# rk1robot_v0_5.net
KiCad netlist of a schematic drawn in EAGLE
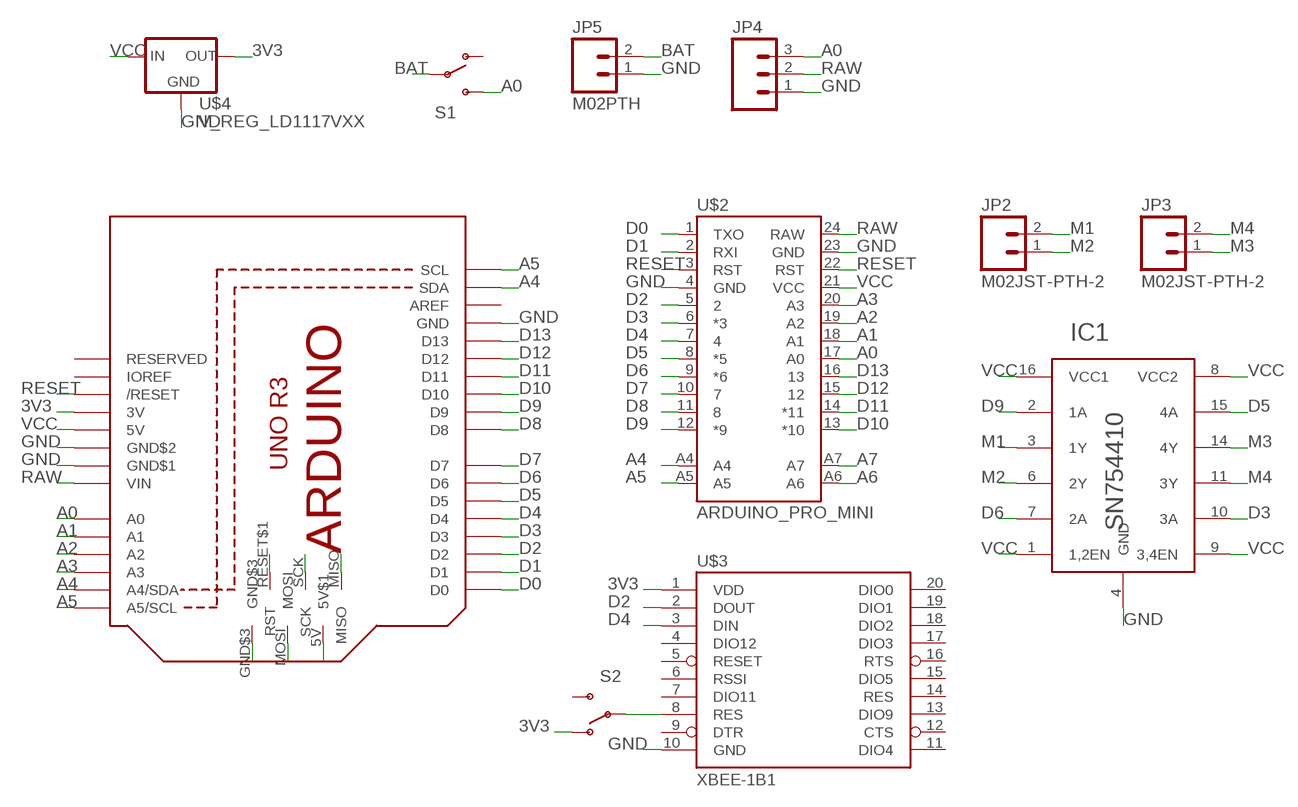
[diagram p0: schematic, sheet 1]

(export (version "E")
  (design (tool "Eeschema 10.0.6"))
  (components
    (comp (ref "IC1")
      (value "SN754410")
      (footprint "eagle-import:DIL16")
      (libsource (lib "eagle-import") (part "SN754410"))
    )
    (comp (ref "JP2")
      (value "M02JST-PTH-2")
      (footprint "eagle-import:JST-2-PTH")
      (libsource (lib "eagle-import") (part "M02JST-PTH-2"))
    )
    (comp (ref "JP3")
      (value "M02JST-PTH-2")
      (footprint "eagle-import:JST-2-PTH")
      (libsource (lib "eagle-import") (part "M02JST-PTH-2"))
    )
    (comp (ref "JP4")
      (value "M03PTH")
      (footprint "eagle-import:1X03")
      (libsource (lib "eagle-import") (part "M03PTH"))
    )
    (comp (ref "JP5")
      (value "M02PTH")
      (footprint "eagle-import:1X02")
      (libsource (lib "eagle-import") (part "M02PTH"))
    )
    (comp (ref "S1")
      (value "SWITCH-SPDTPTH")
      (footprint "eagle-import:SWITCH-SPDT")
      (libsource (lib "eagle-import") (part "SWITCH-SPDTPTH"))
    )
    (comp (ref "S2")
      (value "SWITCH-SPDTPTH")
      (footprint "eagle-import:SWITCH-SPDT")
      (libsource (lib "eagle-import") (part "SWITCH-SPDTPTH"))
    )
    (comp (ref "U$1")
      (value "ARDUINO_R3_ICSP")
      (footprint "eagle-import:ARDUINOR3_ICSP")
      (libsource (lib "eagle-import") (part "ARDUINO_R3_ICSP"))
    )
    (comp (ref "U$2")
      (value "ARDUINO_PRO_MINI")
      (footprint "eagle-import:ARDUINO_PRO_MINI")
      (libsource (lib "eagle-import") (part "ARDUINO_PRO_MINI"))
    )
    (comp (ref "U$3")
      (value "XBEE-1B1")
      (footprint "eagle-import:XBEE-1")
      (libsource (lib "eagle-import") (part "XBEE-1B1"))
    )
    (comp (ref "U$4")
      (value "V_REG_LD1117VXX")
      (footprint "eagle-import:78XXL")
      (libsource (lib "eagle-import") (part "V_REG_LD1117VXX"))
    )
  )
  (nets
    (net (code "1") (name "/3V3") (class "Default")
      (node (ref "S2") (pin "1") (pinfunction "O_1") (pintype "passive"))
      (node (ref "U$1") (pin "3V") (pinfunction "3V_3V") (pintype "power_in"))
      (node (ref "U$3") (pin "1") (pinfunction "VDD_1") (pintype "power_in"))
      (node (ref "U$4") (pin "GND") (pinfunction "OUT_GND") (pintype "output"))
    )
    (net (code "2") (name "/A0") (class "Default")
      (node (ref "JP4") (pin "3") (pinfunction "3_3") (pintype "passive"))
      (node (ref "S1") (pin "3") (pinfunction "S_3") (pintype "passive"))
      (node (ref "U$1") (pin "A0") (pinfunction "A0_A0") (pintype "bidirectional"))
      (node (ref "U$2") (pin "17") (pinfunction "A0_17") (pintype "bidirectional"))
    )
    (net (code "3") (name "/A1") (class "Default")
      (node (ref "U$1") (pin "A1") (pinfunction "A1_A1") (pintype "bidirectional"))
      (node (ref "U$2") (pin "18") (pinfunction "A1_18") (pintype "bidirectional"))
    )
    (net (code "4") (name "/A2") (class "Default")
      (node (ref "U$1") (pin "A2") (pinfunction "A2_A2") (pintype "bidirectional"))
      (node (ref "U$2") (pin "19") (pinfunction "A2_19") (pintype "bidirectional"))
    )
    (net (code "5") (name "/A3") (class "Default")
      (node (ref "U$1") (pin "A3") (pinfunction "A3_A3") (pintype "bidirectional"))
      (node (ref "U$2") (pin "20") (pinfunction "A3_20") (pintype "bidirectional"))
    )
    (net (code "6") (name "/A4") (class "Default")
      (node (ref "U$1") (pin "A4") (pinfunction "A4/SDA_A4") (pintype "bidirectional"))
      (node (ref "U$1") (pin "SDA") (pinfunction "SDA_SDA") (pintype "bidirectional"))
      (node (ref "U$2") (pin "A4") (pinfunction "A4_A4") (pintype "bidirectional"))
    )
    (net (code "7") (name "/A5") (class "Default")
      (node (ref "U$1") (pin "A5") (pinfunction "A5/SCL_A5") (pintype "bidirectional"))
      (node (ref "U$1") (pin "SCL") (pinfunction "SCL_SCL") (pintype "bidirectional"))
      (node (ref "U$2") (pin "A5") (pinfunction "A5_A5") (pintype "bidirectional"))
    )
    (net (code "8") (name "/A6") (class "Default")
      (node (ref "U$2") (pin "A6") (pinfunction "A6_A6") (pintype "bidirectional"))
    )
    (net (code "9") (name "/A7") (class "Default")
      (node (ref "U$2") (pin "A7") (pinfunction "A7_A7") (pintype "bidirectional"))
    )
    (net (code "10") (name "/BAT") (class "Default")
      (node (ref "JP5") (pin "2") (pinfunction "2_2") (pintype "passive"))
      (node (ref "S1") (pin "2") (pinfunction "P_2") (pintype "passive"))
    )
    (net (code "11") (name "/D0") (class "Default")
      (node (ref "U$1") (pin "D0") (pinfunction "D0_D0") (pintype "bidirectional"))
      (node (ref "U$2") (pin "1") (pinfunction "TXO_1") (pintype "bidirectional"))
    )
    (net (code "12") (name "/D1") (class "Default")
      (node (ref "U$1") (pin "D1") (pinfunction "D1_D1") (pintype "bidirectional"))
      (node (ref "U$2") (pin "2") (pinfunction "RXI_2") (pintype "bidirectional"))
    )
    (net (code "13") (name "/D2") (class "Default")
      (node (ref "U$1") (pin "D2") (pinfunction "D2_D2") (pintype "bidirectional"))
      (node (ref "U$2") (pin "5") (pinfunction "2_5") (pintype "bidirectional"))
      (node (ref "U$3") (pin "2") (pinfunction "DOUT_2") (pintype "output"))
    )
    (net (code "14") (name "/D3") (class "Default")
      (node (ref "IC1") (pin "10") (pinfunction "3A_10") (pintype "bidirectional"))
      (node (ref "U$1") (pin "D3") (pinfunction "D3_D3") (pintype "bidirectional"))
      (node (ref "U$2") (pin "6") (pinfunction "*3_6") (pintype "bidirectional"))
    )
    (net (code "15") (name "/D4") (class "Default")
      (node (ref "U$1") (pin "D4") (pinfunction "D4_D4") (pintype "bidirectional"))
      (node (ref "U$2") (pin "7") (pinfunction "4_7") (pintype "bidirectional"))
      (node (ref "U$3") (pin "3") (pinfunction "DIN_3") (pintype "input"))
    )
    (net (code "16") (name "/D5") (class "Default")
      (node (ref "IC1") (pin "15") (pinfunction "4A_15") (pintype "bidirectional"))
      (node (ref "U$1") (pin "D5") (pinfunction "D5_D5") (pintype "bidirectional"))
      (node (ref "U$2") (pin "8") (pinfunction "*5_8") (pintype "bidirectional"))
    )
    (net (code "17") (name "/D6") (class "Default")
      (node (ref "IC1") (pin "7") (pinfunction "2A_7") (pintype "bidirectional"))
      (node (ref "U$1") (pin "D6") (pinfunction "D6_D6") (pintype "bidirectional"))
      (node (ref "U$2") (pin "9") (pinfunction "*6_9") (pintype "bidirectional"))
    )
    (net (code "18") (name "/D7") (class "Default")
      (node (ref "U$1") (pin "D7") (pinfunction "D7_D7") (pintype "bidirectional"))
      (node (ref "U$2") (pin "10") (pinfunction "7_10") (pintype "bidirectional"))
    )
    (net (code "19") (name "/D8") (class "Default")
      (node (ref "U$1") (pin "D8") (pinfunction "D8_D8") (pintype "bidirectional"))
      (node (ref "U$2") (pin "11") (pinfunction "8_11") (pintype "bidirectional"))
    )
    (net (code "20") (name "/D9") (class "Default")
      (node (ref "IC1") (pin "2") (pinfunction "1A_2") (pintype "bidirectional"))
      (node (ref "U$1") (pin "D9") (pinfunction "D9_D9") (pintype "bidirectional"))
      (node (ref "U$2") (pin "12") (pinfunction "*9_12") (pintype "bidirectional"))
    )
    (net (code "21") (name "/D10") (class "Default")
      (node (ref "U$1") (pin "D10") (pinfunction "D10_D10") (pintype "bidirectional"))
      (node (ref "U$2") (pin "13") (pinfunction "*10_13") (pintype "bidirectional"))
    )
    (net (code "22") (name "/D11") (class "Default")
      (node (ref "U$1") (pin "D11") (pinfunction "D11_D11") (pintype "bidirectional"))
      (node (ref "U$1") (pin "MOSI") (pinfunction "MOSI_MOSI") (pintype "passive"))
      (node (ref "U$2") (pin "14") (pinfunction "*11_14") (pintype "bidirectional"))
    )
    (net (code "23") (name "/D12") (class "Default")
      (node (ref "U$1") (pin "D12") (pinfunction "D12_D12") (pintype "bidirectional"))
      (node (ref "U$1") (pin "MISO") (pinfunction "MISO_MISO") (pintype "passive"))
      (node (ref "U$2") (pin "15") (pinfunction "12_15") (pintype "bidirectional"))
    )
    (net (code "24") (name "/D13") (class "Default")
      (node (ref "U$1") (pin "D13") (pinfunction "D13_D13") (pintype "bidirectional"))
      (node (ref "U$1") (pin "SCK") (pinfunction "SCK_SCK") (pintype "passive"))
      (node (ref "U$2") (pin "16") (pinfunction "13_16") (pintype "bidirectional"))
    )
    (net (code "25") (name "/GND") (class "Default")
      (node (ref "IC1") (pin "4") (pinfunction "GND_4") (pintype "power_in"))
      (node (ref "JP4") (pin "1") (pinfunction "1_1") (pintype "passive"))
      (node (ref "JP5") (pin "1") (pinfunction "1_1") (pintype "passive"))
      (node (ref "U$1") (pin "GND") (pinfunction "GND_GND") (pintype "power_in"))
      (node (ref "U$1") (pin "GND$1") (pinfunction "GND$1_GND$1") (pintype "power_in"))
      (node (ref "U$1") (pin "GND$2") (pinfunction "GND$2_GND$2") (pintype "power_in"))
      (node (ref "U$1") (pin "GND$3") (pinfunction "GND$3_GND$3") (pintype "passive"))
      (node (ref "U$2") (pin "23") (pinfunction "GND_23") (pintype "bidirectional"))
      (node (ref "U$2") (pin "4") (pinfunction "GND_4") (pintype "bidirectional"))
      (node (ref "U$3") (pin "10") (pinfunction "GND_10") (pintype "power_in"))
      (node (ref "U$4") (pin "IN") (pinfunction "GND_IN") (pintype "input"))
    )
    (net (code "26") (name "/M1") (class "Default")
      (node (ref "IC1") (pin "3") (pinfunction "1Y_3") (pintype "bidirectional"))
      (node (ref "JP2") (pin "2") (pinfunction "2_2") (pintype "passive"))
    )
    (net (code "27") (name "/M2") (class "Default")
      (node (ref "IC1") (pin "6") (pinfunction "2Y_6") (pintype "bidirectional"))
      (node (ref "JP2") (pin "1") (pinfunction "1_1") (pintype "passive"))
    )
    (net (code "28") (name "/M3") (class "Default")
      (node (ref "IC1") (pin "14") (pinfunction "4Y_14") (pintype "bidirectional"))
      (node (ref "JP3") (pin "1") (pinfunction "1_1") (pintype "passive"))
    )
    (net (code "29") (name "/M4") (class "Default")
      (node (ref "IC1") (pin "11") (pinfunction "3Y_11") (pintype "bidirectional"))
      (node (ref "JP3") (pin "2") (pinfunction "2_2") (pintype "passive"))
    )
    (net (code "30") (name "/RAW") (class "Default")
      (node (ref "JP4") (pin "2") (pinfunction "2_2") (pintype "passive"))
      (node (ref "U$1") (pin "VIN") (pinfunction "VIN_VIN") (pintype "power_in"))
      (node (ref "U$2") (pin "24") (pinfunction "RAW_24") (pintype "bidirectional"))
    )
    (net (code "31") (name "/RESET") (class "Default")
      (node (ref "U$1") (pin "RESET") (pinfunction "/RESET_RESET") (pintype "bidirectional"))
      (node (ref "U$1") (pin "RESET$1") (pinfunction "RST_RESET$1") (pintype "passive"))
      (node (ref "U$2") (pin "22") (pinfunction "RST_22") (pintype "bidirectional"))
      (node (ref "U$2") (pin "3") (pinfunction "RST_3") (pintype "bidirectional"))
    )
    (net (code "32") (name "/VCC") (class "Default")
      (node (ref "IC1") (pin "1") (pinfunction "1,2EN_1") (pintype "bidirectional"))
      (node (ref "IC1") (pin "16") (pinfunction "VCC1_16") (pintype "power_in"))
      (node (ref "IC1") (pin "8") (pinfunction "VCC2_8") (pintype "power_in"))
      (node (ref "IC1") (pin "9") (pinfunction "3,4EN_9") (pintype "bidirectional"))
      (node (ref "U$1") (pin "+5V") (pinfunction "5V_+5V") (pintype "power_in"))
      (node (ref "U$1") (pin "5V") (pinfunction "5V$1_5V") (pintype "passive"))
      (node (ref "U$2") (pin "21") (pinfunction "VCC_21") (pintype "bidirectional"))
      (node (ref "U$4") (pin "OUT") (pinfunction "IN_OUT") (pintype "input"))
    )
    (net (code "33") (name "Net-(S2-P)") (class "Default")
      (node (ref "S2") (pin "2") (pinfunction "P_2") (pintype "passive"))
      (node (ref "U$3") (pin "8") (pinfunction "RES_8") (pintype "bidirectional"))
    )
    (net (code "34") (name "unconnected-(S1-O-Pad1)") (class "Default")
      (node (ref "S1") (pin "1") (pinfunction "O_1") (pintype "passive"))
    )
    (net (code "35") (name "unconnected-(S2-S-Pad3)") (class "Default")
      (node (ref "S2") (pin "3") (pinfunction "S_3") (pintype "passive"))
    )
    (net (code "36") (name "unconnected-(U$1-PadAREF)") (class "Default")
      (node (ref "U$1") (pin "AREF") (pinfunction "AREF_AREF") (pintype "bidirectional"))
    )
    (net (code "37") (name "unconnected-(U$1-PadIOREF)") (class "Default")
      (node (ref "U$1") (pin "IOREF") (pinfunction "IOREF_IOREF") (pintype "output"))
    )
    (net (code "38") (name "unconnected-(U$1-PadRESERVED)") (class "Default")
      (node (ref "U$1") (pin "RESERVED") (pinfunction "RESERVED_RESERVED") (pintype "no_connect"))
    )
    (net (code "39") (name "unconnected-(U$3-CTS-Pad12)") (class "Default")
      (node (ref "U$3") (pin "12") (pinfunction "CTS_12") (pintype "output"))
    )
    (net (code "40") (name "unconnected-(U$3-DIO0-Pad20)") (class "Default")
      (node (ref "U$3") (pin "20") (pinfunction "DIO0_20") (pintype "bidirectional"))
    )
    (net (code "41") (name "unconnected-(U$3-DIO1-Pad19)") (class "Default")
      (node (ref "U$3") (pin "19") (pinfunction "DIO1_19") (pintype "bidirectional"))
    )
    (net (code "42") (name "unconnected-(U$3-DIO2-Pad18)") (class "Default")
      (node (ref "U$3") (pin "18") (pinfunction "DIO2_18") (pintype "bidirectional"))
    )
    (net (code "43") (name "unconnected-(U$3-DIO3-Pad17)") (class "Default")
      (node (ref "U$3") (pin "17") (pinfunction "DIO3_17") (pintype "bidirectional"))
    )
    (net (code "44") (name "unconnected-(U$3-DIO4-Pad11)") (class "Default")
      (node (ref "U$3") (pin "11") (pinfunction "DIO4_11") (pintype "bidirectional"))
    )
    (net (code "45") (name "unconnected-(U$3-DIO5-Pad15)") (class "Default")
      (node (ref "U$3") (pin "15") (pinfunction "DIO5_15") (pintype "bidirectional"))
    )
    (net (code "46") (name "unconnected-(U$3-DIO9-Pad13)") (class "Default")
      (node (ref "U$3") (pin "13") (pinfunction "DIO9_13") (pintype "bidirectional"))
    )
    (net (code "47") (name "unconnected-(U$3-DIO11-Pad7)") (class "Default")
      (node (ref "U$3") (pin "7") (pinfunction "DIO11_7") (pintype "bidirectional"))
    )
    (net (code "48") (name "unconnected-(U$3-DIO12-Pad4)") (class "Default")
      (node (ref "U$3") (pin "4") (pinfunction "DIO12_4") (pintype "bidirectional"))
    )
    (net (code "49") (name "unconnected-(U$3-DTR-Pad9)") (class "Default")
      (node (ref "U$3") (pin "9") (pinfunction "DTR_9") (pintype "bidirectional"))
    )
    (net (code "50") (name "unconnected-(U$3-RES-Pad14)") (class "Default")
      (node (ref "U$3") (pin "14") (pinfunction "RES_14") (pintype "bidirectional"))
    )
    (net (code "51") (name "unconnected-(U$3-RESET-Pad5)") (class "Default")
      (node (ref "U$3") (pin "5") (pinfunction "RESET_5") (pintype "input"))
    )
    (net (code "52") (name "unconnected-(U$3-RSSI-Pad6)") (class "Default")
      (node (ref "U$3") (pin "6") (pinfunction "RSSI_6") (pintype "bidirectional"))
    )
    (net (code "53") (name "unconnected-(U$3-RTS-Pad16)") (class "Default")
      (node (ref "U$3") (pin "16") (pinfunction "RTS_16") (pintype "input"))
    )
  )
)
